# Mainboard_Debug_Interface.net
KiCad netlist of a schematic drawn in Altium Designer
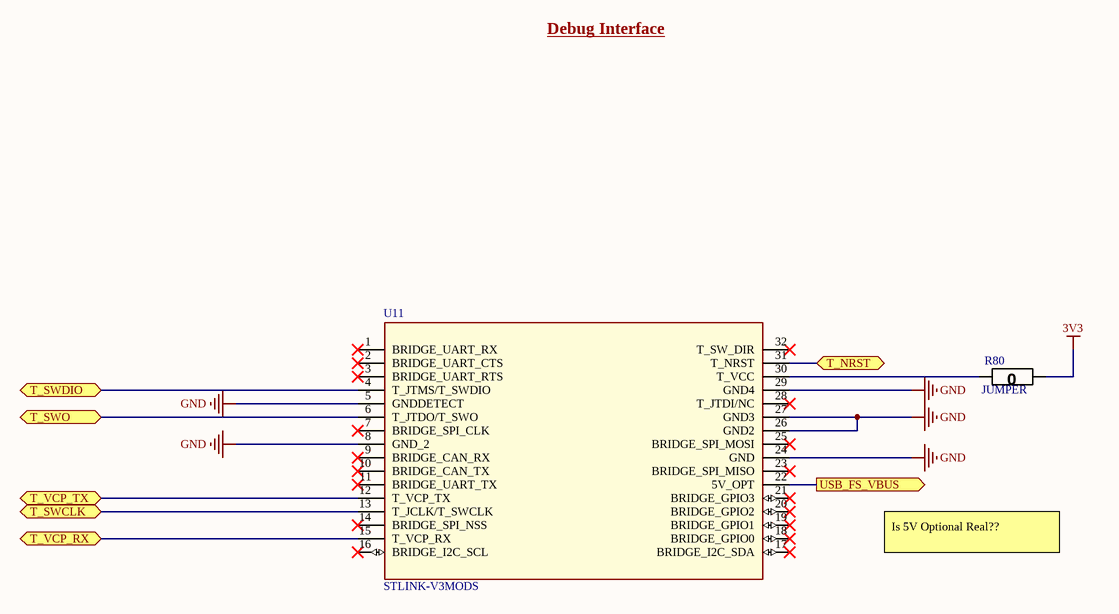
[diagram p0: Mainboard_Debug_Interface.SchDoc]

(export (version "E")
  (design (tool "Eeschema 10.0.6"))
  (components
    (comp (ref "R80")
      (value "JUMPER")
      (footprint "0805")
      (description "RES SMD 0 OHM JUMPER GENERIC 0805")
      (libsource (lib "AltiumLibraries") (part "RES 0 JUMPER"))
    )
    (comp (ref "U11")
      (value "STLINK-V3MODS")
      (footprint "STLINK-V3MODS")
      (description "STM32 - Debugger, Programmer (In-Circuit/In-System)")
      (fields (field (name "MF") "STMicroelectronics"))
      (libsource (lib "AltiumLibraries") (part "STLINK-V3MODS"))
    )
  )
  (nets
    (net (code "1") (name "/T_NRST") (class "Default")
      (node (ref "U11") (pin "31") (pinfunction "T_NRST_31") (pintype "passive"))
    )
    (net (code "2") (name "/T_SWCLK") (class "Default")
      (node (ref "U11") (pin "13") (pinfunction "T_JCLK/T_SWCLK_13") (pintype "passive"))
    )
    (net (code "3") (name "/T_SWDIO") (class "Default")
      (node (ref "U11") (pin "4") (pinfunction "T_JTMS/T_SWDIO_4") (pintype "passive"))
    )
    (net (code "4") (name "/T_SWO") (class "Default")
      (node (ref "U11") (pin "6") (pinfunction "T_JTDO/T_SWO_6") (pintype "passive"))
    )
    (net (code "5") (name "/T_VCP_RX") (class "Default")
      (node (ref "U11") (pin "15") (pinfunction "T_VCP_RX_15") (pintype "passive"))
    )
    (net (code "6") (name "/T_VCP_TX") (class "Default")
      (node (ref "U11") (pin "12") (pinfunction "T_VCP_TX_12") (pintype "passive"))
    )
    (net (code "7") (name "/USB_FS_VBUS") (class "Default")
      (node (ref "U11") (pin "22") (pinfunction "5V_OPT_22") (pintype "passive"))
    )
    (net (code "8") (name "3V3") (class "Default")
      (node (ref "R80") (pin "1") (pinfunction "R1_1") (pintype "passive"))
    )
    (net (code "9") (name "GND") (class "Default")
      (node (ref "U11") (pin "24") (pinfunction "GND_24") (pintype "passive"))
      (node (ref "U11") (pin "26") (pinfunction "GND2_26") (pintype "passive"))
      (node (ref "U11") (pin "27") (pinfunction "GND3_27") (pintype "passive"))
      (node (ref "U11") (pin "29") (pinfunction "GND4_29") (pintype "passive"))
      (node (ref "U11") (pin "5") (pinfunction "GNDDETECT_5") (pintype "passive"))
      (node (ref "U11") (pin "8") (pinfunction "GND_2_8") (pintype "passive"))
    )
    (net (code "10") (name "Net-(R80-R2)") (class "Default")
      (node (ref "R80") (pin "2") (pinfunction "R2_2") (pintype "passive"))
      (node (ref "U11") (pin "30") (pinfunction "T_VCC_30") (pintype "passive"))
    )
    (net (code "11") (name "unconnected-(U11-BRIDGE_CAN_RX-Pad9)") (class "Default")
      (node (ref "U11") (pin "9") (pinfunction "BRIDGE_CAN_RX_9") (pintype "passive+no_connect"))
    )
    (net (code "12") (name "unconnected-(U11-BRIDGE_CAN_TX-Pad10)") (class "Default")
      (node (ref "U11") (pin "10") (pinfunction "BRIDGE_CAN_TX_10") (pintype "passive+no_connect"))
    )
    (net (code "13") (name "unconnected-(U11-BRIDGE_GPIO0-Pad18)") (class "Default")
      (node (ref "U11") (pin "18") (pinfunction "BRIDGE_GPIO0_18") (pintype "bidirectional+no_connect"))
    )
    (net (code "14") (name "unconnected-(U11-BRIDGE_GPIO1-Pad19)") (class "Default")
      (node (ref "U11") (pin "19") (pinfunction "BRIDGE_GPIO1_19") (pintype "bidirectional+no_connect"))
    )
    (net (code "15") (name "unconnected-(U11-BRIDGE_GPIO2-Pad20)") (class "Default")
      (node (ref "U11") (pin "20") (pinfunction "BRIDGE_GPIO2_20") (pintype "bidirectional+no_connect"))
    )
    (net (code "16") (name "unconnected-(U11-BRIDGE_GPIO3-Pad21)") (class "Default")
      (node (ref "U11") (pin "21") (pinfunction "BRIDGE_GPIO3_21") (pintype "bidirectional+no_connect"))
    )
    (net (code "17") (name "unconnected-(U11-BRIDGE_I2C_SCL-Pad16)") (class "Default")
      (node (ref "U11") (pin "16") (pinfunction "BRIDGE_I2C_SCL_16") (pintype "bidirectional+no_connect"))
    )
    (net (code "18") (name "unconnected-(U11-BRIDGE_I2C_SDA-Pad17)") (class "Default")
      (node (ref "U11") (pin "17") (pinfunction "BRIDGE_I2C_SDA_17") (pintype "bidirectional+no_connect"))
    )
    (net (code "19") (name "unconnected-(U11-BRIDGE_SPI_CLK-Pad7)") (class "Default")
      (node (ref "U11") (pin "7") (pinfunction "BRIDGE_SPI_CLK_7") (pintype "passive+no_connect"))
    )
    (net (code "20") (name "unconnected-(U11-BRIDGE_SPI_MISO-Pad23)") (class "Default")
      (node (ref "U11") (pin "23") (pinfunction "BRIDGE_SPI_MISO_23") (pintype "passive+no_connect"))
    )
    (net (code "21") (name "unconnected-(U11-BRIDGE_SPI_MOSI-Pad25)") (class "Default")
      (node (ref "U11") (pin "25") (pinfunction "BRIDGE_SPI_MOSI_25") (pintype "passive+no_connect"))
    )
    (net (code "22") (name "unconnected-(U11-BRIDGE_SPI_NSS-Pad14)") (class "Default")
      (node (ref "U11") (pin "14") (pinfunction "BRIDGE_SPI_NSS_14") (pintype "passive+no_connect"))
    )
    (net (code "23") (name "unconnected-(U11-BRIDGE_UART_CTS-Pad2)") (class "Default")
      (node (ref "U11") (pin "2") (pinfunction "BRIDGE_UART_CTS_2") (pintype "passive+no_connect"))
    )
    (net (code "24") (name "unconnected-(U11-BRIDGE_UART_RTS-Pad3)") (class "Default")
      (node (ref "U11") (pin "3") (pinfunction "BRIDGE_UART_RTS_3") (pintype "passive+no_connect"))
    )
    (net (code "25") (name "unconnected-(U11-BRIDGE_UART_RX-Pad1)") (class "Default")
      (node (ref "U11") (pin "1") (pinfunction "BRIDGE_UART_RX_1") (pintype "passive+no_connect"))
    )
    (net (code "26") (name "unconnected-(U11-BRIDGE_UART_TX-Pad11)") (class "Default")
      (node (ref "U11") (pin "11") (pinfunction "BRIDGE_UART_TX_11") (pintype "passive+no_connect"))
    )
    (net (code "27") (name "unconnected-(U11-T_JTDI{slash}NC-Pad28)") (class "Default")
      (node (ref "U11") (pin "28") (pinfunction "T_JTDI/NC_28") (pintype "passive+no_connect"))
    )
    (net (code "28") (name "unconnected-(U11-T_SW_DIR-Pad32)") (class "Default")
      (node (ref "U11") (pin "32") (pinfunction "T_SW_DIR_32") (pintype "passive+no_connect"))
    )
  )
)
